# Rocket-Control3.net
KiCad netlist of a schematic drawn in EAGLE
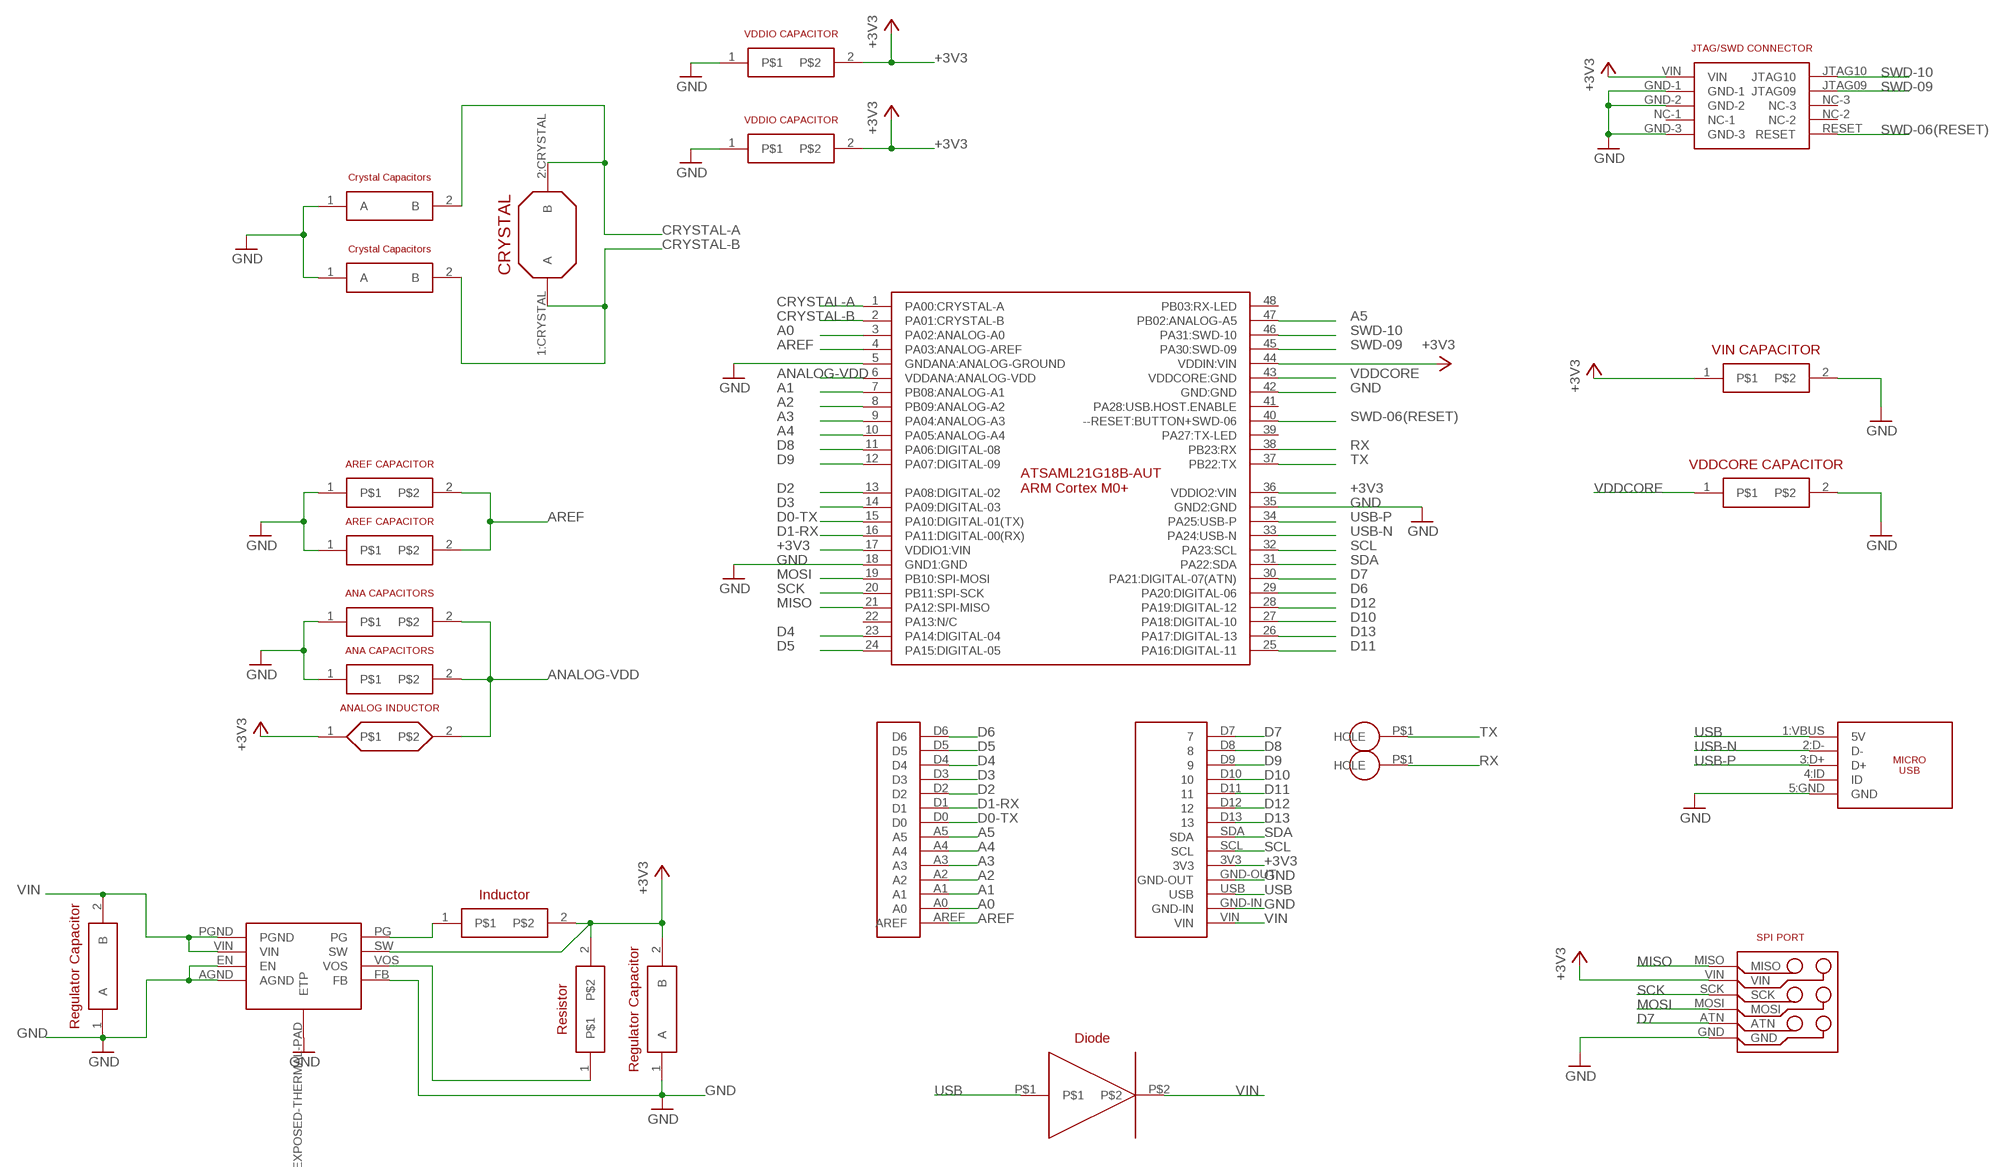
[diagram p0: schematic, sheet 1]

(export (version "E")
  (design (tool "Eeschema 10.0.6"))
  (components
    (comp (ref "U$1")
      (value "ATSAML21G18B-AUT")
      (footprint "eagle-import:TQFP48")
      (libsource (lib "eagle-import") (part "ATSAML21G18B-AUT"))
    )
    (comp (ref "U$2")
      (value "CRYSTAL-CAPACITORS")
      (footprint "eagle-import:C0603")
      (libsource (lib "eagle-import") (part "CRYSTAL-CAPACITORS"))
    )
    (comp (ref "U$3")
      (value "CRYSTAL-CAPACITORS")
      (footprint "eagle-import:C0603")
      (libsource (lib "eagle-import") (part "CRYSTAL-CAPACITORS"))
    )
    (comp (ref "U$4")
      (value "CRYSTAL")
      (footprint "eagle-import:4-SOJ_CRYSTAL")
      (libsource (lib "eagle-import") (part "CRYSTAL"))
    )
    (comp (ref "U$5")
      (value "REGULATOR")
      (footprint "eagle-import:8-WFDFN-EXPOSED-PAD")
      (libsource (lib "eagle-import") (part "REGULATOR"))
    )
    (comp (ref "U$6")
      (value "AREF-CAPACITORS")
      (footprint "eagle-import:C0603")
      (libsource (lib "eagle-import") (part "AREF-CAPACITORS"))
    )
    (comp (ref "U$7")
      (value "AREF-CAPACITORS")
      (footprint "eagle-import:C0603")
      (libsource (lib "eagle-import") (part "AREF-CAPACITORS"))
    )
    (comp (ref "U$8")
      (value "ANALOG-CAPACITORS")
      (footprint "eagle-import:C0603")
      (libsource (lib "eagle-import") (part "ANALOG-CAPACITORS"))
    )
    (comp (ref "U$9")
      (value "ANALOG-CAPACITORS")
      (footprint "eagle-import:C0603")
      (libsource (lib "eagle-import") (part "ANALOG-CAPACITORS"))
    )
    (comp (ref "U$10")
      (value "ANALOG-INDUCTOR")
      (footprint "eagle-import:C0603")
      (libsource (lib "eagle-import") (part "ANALOG-INDUCTOR"))
    )
    (comp (ref "U$11")
      (value "REGULATOR-CAPACITORS")
      (footprint "eagle-import:C0603")
      (libsource (lib "eagle-import") (part "REGULATOR-CAPACITORS"))
    )
    (comp (ref "U$12")
      (value "REGULATOR-CAPACITORS")
      (footprint "eagle-import:C0603")
      (libsource (lib "eagle-import") (part "REGULATOR-CAPACITORS"))
    )
    (comp (ref "U$13")
      (value "REGULATOR-INDUCTOR")
      (footprint "eagle-import:C0603")
      (libsource (lib "eagle-import") (part "REGULATOR-INDUCTOR"))
    )
    (comp (ref "U$14")
      (value "REGULATOR-RESISTOR")
      (footprint "eagle-import:C0603")
      (libsource (lib "eagle-import") (part "REGULATOR-RESISTOR"))
    )
    (comp (ref "U$15")
      (value "REGULATION-DIODE")
      (footprint "eagle-import:SOD-882")
      (libsource (lib "eagle-import") (part "REGULATION-DIODE"))
    )
    (comp (ref "U$16")
      (value "HEADER-HOLE")
      (footprint "eagle-import:HEADER-HOLE")
      (libsource (lib "eagle-import") (part "HEADER-HOLE"))
    )
    (comp (ref "U$17")
      (value "HEADER-HOLE")
      (footprint "eagle-import:HEADER-HOLE")
      (libsource (lib "eagle-import") (part "HEADER-HOLE"))
    )
    (comp (ref "U$21")
      (value "HEADER-SIDE-A")
      (footprint "eagle-import:HEADER-SIDE-A")
      (libsource (lib "eagle-import") (part "HEADER-SIDE-A"))
    )
    (comp (ref "U$22")
      (value "HEADER-SIDE-B")
      (footprint "eagle-import:HEADER-SIDE-B")
      (libsource (lib "eagle-import") (part "HEADER-SIDE-B"))
    )
    (comp (ref "U$26")
      (value "VDDIO-CAPACITOR")
      (footprint "eagle-import:C0402")
      (libsource (lib "eagle-import") (part "VDDIO-CAPACITOR"))
    )
    (comp (ref "U$35")
      (value "VDDIO-CAPACITOR")
      (footprint "eagle-import:C0402")
      (libsource (lib "eagle-import") (part "VDDIO-CAPACITOR"))
    )
    (comp (ref "U$38")
      (value "10118194-0001LF:MICRO-USB")
      (footprint "eagle-import:10118194-0001LF_MICRO-USB-B")
      (libsource (lib "eagle-import") (part "10118194-0001LF{colon}MICRO-USB"))
    )
    (comp (ref "U$41")
      (value "SPI-PORT")
      (footprint "eagle-import:SPI-PORT")
      (libsource (lib "eagle-import") (part "SPI-PORT"))
    )
    (comp (ref "U$56")
      (value "VDDCORE-CAPACITOR")
      (footprint "eagle-import:C0603")
      (libsource (lib "eagle-import") (part "VDDCORE-CAPACITOR"))
    )
    (comp (ref "U$57")
      (value "VIN-CAPACITOR")
      (footprint "eagle-import:C0603")
      (libsource (lib "eagle-import") (part "VIN-CAPACITOR"))
    )
    (comp (ref "U$61")
      (value "JTAG-MINI")
      (footprint "eagle-import:JTAG-MINI")
      (libsource (lib "eagle-import") (part "JTAG-MINI"))
    )
  )
  (nets
    (net (code "1") (name "+3V3") (class "Default")
      (node (ref "U$1") (pin "17") (pinfunction "VDDIO1:VIN_17") (pintype "bidirectional"))
      (node (ref "U$1") (pin "36") (pinfunction "VDDIO2:VIN_36") (pintype "bidirectional"))
      (node (ref "U$1") (pin "44") (pinfunction "VDDIN:VIN_44") (pintype "bidirectional"))
      (node (ref "U$10") (pin "1") (pinfunction "P$1_1") (pintype "bidirectional"))
      (node (ref "U$12") (pin "2") (pinfunction "B_2") (pintype "bidirectional"))
      (node (ref "U$13") (pin "2") (pinfunction "P$2_2") (pintype "bidirectional"))
      (node (ref "U$14") (pin "2") (pinfunction "P$2_2") (pintype "bidirectional"))
      (node (ref "U$22") (pin "3V3") (pinfunction "3V3_3V3") (pintype "bidirectional"))
      (node (ref "U$26") (pin "2") (pinfunction "P$2_2") (pintype "bidirectional"))
      (node (ref "U$35") (pin "2") (pinfunction "P$2_2") (pintype "bidirectional"))
      (node (ref "U$41") (pin "VIN") (pinfunction "VIN_VIN") (pintype "bidirectional"))
      (node (ref "U$5") (pin "SW") (pinfunction "SW_SW") (pintype "bidirectional"))
      (node (ref "U$57") (pin "1") (pinfunction "P$1_1") (pintype "bidirectional"))
      (node (ref "U$61") (pin "VIN") (pinfunction "VIN_VIN") (pintype "bidirectional"))
    )
    (net (code "2") (name "/A0") (class "Default")
      (node (ref "U$1") (pin "3") (pinfunction "PA02:ANALOG-A0_3") (pintype "bidirectional"))
      (node (ref "U$21") (pin "A0") (pinfunction "A0_A0") (pintype "bidirectional"))
    )
    (net (code "3") (name "/A1") (class "Default")
      (node (ref "U$1") (pin "7") (pinfunction "PB08:ANALOG-A1_7") (pintype "bidirectional"))
      (node (ref "U$21") (pin "A1") (pinfunction "A1_A1") (pintype "bidirectional"))
    )
    (net (code "4") (name "/A2") (class "Default")
      (node (ref "U$1") (pin "8") (pinfunction "PB09:ANALOG-A2_8") (pintype "bidirectional"))
      (node (ref "U$21") (pin "A2") (pinfunction "A2_A2") (pintype "bidirectional"))
    )
    (net (code "5") (name "/A3") (class "Default")
      (node (ref "U$1") (pin "9") (pinfunction "PA04:ANALOG-A3_9") (pintype "bidirectional"))
      (node (ref "U$21") (pin "A3") (pinfunction "A3_A3") (pintype "bidirectional"))
    )
    (net (code "6") (name "/A4") (class "Default")
      (node (ref "U$1") (pin "10") (pinfunction "PA05:ANALOG-A4_10") (pintype "bidirectional"))
      (node (ref "U$21") (pin "A4") (pinfunction "A4_A4") (pintype "bidirectional"))
    )
    (net (code "7") (name "/A5") (class "Default")
      (node (ref "U$1") (pin "47") (pinfunction "PB02:ANALOG-A5_47") (pintype "bidirectional"))
      (node (ref "U$21") (pin "A5") (pinfunction "A5_A5") (pintype "bidirectional"))
    )
    (net (code "8") (name "/ANALOG-VDD") (class "Default")
      (node (ref "U$1") (pin "6") (pinfunction "VDDANA:ANALOG-VDD_6") (pintype "bidirectional"))
      (node (ref "U$10") (pin "2") (pinfunction "P$2_2") (pintype "bidirectional"))
      (node (ref "U$8") (pin "2") (pinfunction "P$2_2") (pintype "bidirectional"))
      (node (ref "U$9") (pin "2") (pinfunction "P$2_2") (pintype "bidirectional"))
    )
    (net (code "9") (name "/AREF") (class "Default")
      (node (ref "U$1") (pin "4") (pinfunction "PA03:ANALOG-AREF_4") (pintype "bidirectional"))
      (node (ref "U$21") (pin "AREF") (pinfunction "AREF_AREF") (pintype "bidirectional"))
      (node (ref "U$6") (pin "2") (pinfunction "P$2_2") (pintype "bidirectional"))
      (node (ref "U$7") (pin "2") (pinfunction "P$2_2") (pintype "bidirectional"))
    )
    (net (code "10") (name "/CRYSTAL-A") (class "Default")
      (node (ref "U$1") (pin "1") (pinfunction "PA00:CRYSTAL-A_1") (pintype "bidirectional"))
      (node (ref "U$2") (pin "2") (pinfunction "B_2") (pintype "bidirectional"))
      (node (ref "U$4") (pin "2:CRYSTAL") (pinfunction "B_2:CRYSTAL") (pintype "bidirectional"))
    )
    (net (code "11") (name "/CRYSTAL-B") (class "Default")
      (node (ref "U$1") (pin "2") (pinfunction "PA01:CRYSTAL-B_2") (pintype "bidirectional"))
      (node (ref "U$3") (pin "2") (pinfunction "B_2") (pintype "bidirectional"))
      (node (ref "U$4") (pin "1:CRYSTAL") (pinfunction "A_1:CRYSTAL") (pintype "bidirectional"))
    )
    (net (code "12") (name "/D0-TX") (class "Default")
      (node (ref "U$1") (pin "15") (pinfunction "PA10:DIGITAL-01(TX)_15") (pintype "bidirectional"))
      (node (ref "U$21") (pin "D0") (pinfunction "D0_D0") (pintype "bidirectional"))
    )
    (net (code "13") (name "/D1-RX") (class "Default")
      (node (ref "U$1") (pin "16") (pinfunction "PA11:DIGITAL-00(RX)_16") (pintype "bidirectional"))
      (node (ref "U$21") (pin "D1") (pinfunction "D1_D1") (pintype "bidirectional"))
    )
    (net (code "14") (name "/D2") (class "Default")
      (node (ref "U$1") (pin "13") (pinfunction "PA08:DIGITAL-02_13") (pintype "bidirectional"))
      (node (ref "U$21") (pin "D2") (pinfunction "D2_D2") (pintype "bidirectional"))
    )
    (net (code "15") (name "/D3") (class "Default")
      (node (ref "U$1") (pin "14") (pinfunction "PA09:DIGITAL-03_14") (pintype "bidirectional"))
      (node (ref "U$21") (pin "D3") (pinfunction "D3_D3") (pintype "bidirectional"))
    )
    (net (code "16") (name "/D4") (class "Default")
      (node (ref "U$1") (pin "23") (pinfunction "PA14:DIGITAL-04_23") (pintype "bidirectional"))
      (node (ref "U$21") (pin "D4") (pinfunction "D4_D4") (pintype "bidirectional"))
    )
    (net (code "17") (name "/D5") (class "Default")
      (node (ref "U$1") (pin "24") (pinfunction "PA15:DIGITAL-05_24") (pintype "bidirectional"))
      (node (ref "U$21") (pin "D5") (pinfunction "D5_D5") (pintype "bidirectional"))
    )
    (net (code "18") (name "/D6") (class "Default")
      (node (ref "U$1") (pin "29") (pinfunction "PA20:DIGITAL-06_29") (pintype "bidirectional"))
      (node (ref "U$21") (pin "D6") (pinfunction "D6_D6") (pintype "bidirectional"))
    )
    (net (code "19") (name "/D7") (class "Default")
      (node (ref "U$1") (pin "30") (pinfunction "PA21:DIGITAL-07(ATN)_30") (pintype "bidirectional"))
      (node (ref "U$22") (pin "D7") (pinfunction "7_D7") (pintype "bidirectional"))
      (node (ref "U$41") (pin "ATN") (pinfunction "ATN_ATN") (pintype "bidirectional"))
    )
    (net (code "20") (name "/D8") (class "Default")
      (node (ref "U$1") (pin "11") (pinfunction "PA06:DIGITAL-08_11") (pintype "bidirectional"))
      (node (ref "U$22") (pin "D8") (pinfunction "8_D8") (pintype "bidirectional"))
    )
    (net (code "21") (name "/D9") (class "Default")
      (node (ref "U$1") (pin "12") (pinfunction "PA07:DIGITAL-09_12") (pintype "bidirectional"))
      (node (ref "U$22") (pin "D9") (pinfunction "9_D9") (pintype "bidirectional"))
    )
    (net (code "22") (name "/D10") (class "Default")
      (node (ref "U$1") (pin "27") (pinfunction "PA18:DIGITAL-10_27") (pintype "bidirectional"))
      (node (ref "U$22") (pin "D10") (pinfunction "10_D10") (pintype "bidirectional"))
    )
    (net (code "23") (name "/D11") (class "Default")
      (node (ref "U$1") (pin "25") (pinfunction "PA16:DIGITAL-11_25") (pintype "bidirectional"))
      (node (ref "U$22") (pin "D11") (pinfunction "11_D11") (pintype "bidirectional"))
    )
    (net (code "24") (name "/D12") (class "Default")
      (node (ref "U$1") (pin "28") (pinfunction "PA19:DIGITAL-12_28") (pintype "bidirectional"))
      (node (ref "U$22") (pin "D12") (pinfunction "12_D12") (pintype "bidirectional"))
    )
    (net (code "25") (name "/D13") (class "Default")
      (node (ref "U$1") (pin "26") (pinfunction "PA17:DIGITAL-13_26") (pintype "bidirectional"))
      (node (ref "U$22") (pin "D13") (pinfunction "13_D13") (pintype "bidirectional"))
    )
    (net (code "26") (name "/MISO") (class "Default")
      (node (ref "U$1") (pin "21") (pinfunction "PA12:SPI-MISO_21") (pintype "bidirectional"))
      (node (ref "U$41") (pin "MISO") (pinfunction "MISO_MISO") (pintype "bidirectional"))
    )
    (net (code "27") (name "/MOSI") (class "Default")
      (node (ref "U$1") (pin "19") (pinfunction "PB10:SPI-MOSI_19") (pintype "bidirectional"))
      (node (ref "U$41") (pin "MOSI") (pinfunction "MOSI_MOSI") (pintype "bidirectional"))
    )
    (net (code "28") (name "/RX") (class "Default")
      (node (ref "U$1") (pin "38") (pinfunction "PB23:RX_38") (pintype "bidirectional"))
      (node (ref "U$17") (pin "P$1") (pinfunction "HOLE_P$1") (pintype "bidirectional"))
    )
    (net (code "29") (name "/SCK") (class "Default")
      (node (ref "U$1") (pin "20") (pinfunction "PB11:SPI-SCK_20") (pintype "bidirectional"))
      (node (ref "U$41") (pin "SCK") (pinfunction "SCK_SCK") (pintype "bidirectional"))
    )
    (net (code "30") (name "/SCL") (class "Default")
      (node (ref "U$1") (pin "32") (pinfunction "PA23:SCL_32") (pintype "bidirectional"))
      (node (ref "U$22") (pin "SCL") (pinfunction "SCL_SCL") (pintype "bidirectional"))
    )
    (net (code "31") (name "/SDA") (class "Default")
      (node (ref "U$1") (pin "31") (pinfunction "PA22:SDA_31") (pintype "bidirectional"))
      (node (ref "U$22") (pin "SDA") (pinfunction "SDA_SDA") (pintype "bidirectional"))
    )
    (net (code "32") (name "/SWD-06(RESET)") (class "Default")
      (node (ref "U$1") (pin "40") (pinfunction "--RESET:BUTTON+SWD-06_40") (pintype "bidirectional"))
      (node (ref "U$61") (pin "RESET") (pinfunction "RESET_RESET") (pintype "bidirectional"))
    )
    (net (code "33") (name "/SWD-09") (class "Default")
      (node (ref "U$1") (pin "45") (pinfunction "PA30:SWD-09_45") (pintype "bidirectional"))
      (node (ref "U$61") (pin "JTAG09") (pinfunction "JTAG09_JTAG09") (pintype "bidirectional"))
    )
    (net (code "34") (name "/SWD-10") (class "Default")
      (node (ref "U$1") (pin "46") (pinfunction "PA31:SWD-10_46") (pintype "bidirectional"))
      (node (ref "U$61") (pin "JTAG10") (pinfunction "JTAG10_JTAG10") (pintype "bidirectional"))
    )
    (net (code "35") (name "/TX") (class "Default")
      (node (ref "U$1") (pin "37") (pinfunction "PB22:TX_37") (pintype "bidirectional"))
      (node (ref "U$16") (pin "P$1") (pinfunction "HOLE_P$1") (pintype "bidirectional"))
    )
    (net (code "36") (name "/USB") (class "Default")
      (node (ref "U$15") (pin "P$1") (pinfunction "P$1_P$1") (pintype "bidirectional"))
      (node (ref "U$22") (pin "USB") (pinfunction "USB_USB") (pintype "bidirectional"))
      (node (ref "U$38") (pin "1:VBUS") (pinfunction "5V_1:VBUS") (pintype "bidirectional"))
    )
    (net (code "37") (name "/USB-N") (class "Default")
      (node (ref "U$1") (pin "33") (pinfunction "PA24:USB-N_33") (pintype "bidirectional"))
      (node (ref "U$38") (pin "2:D-") (pinfunction "D-_2:D-") (pintype "bidirectional"))
    )
    (net (code "38") (name "/USB-P") (class "Default")
      (node (ref "U$1") (pin "34") (pinfunction "PA25:USB-P_34") (pintype "bidirectional"))
      (node (ref "U$38") (pin "3:D+") (pinfunction "D+_3:D+") (pintype "bidirectional"))
    )
    (net (code "39") (name "/VDDCORE") (class "Default")
      (node (ref "U$1") (pin "43") (pinfunction "VDDCORE:GND_43") (pintype "bidirectional"))
      (node (ref "U$56") (pin "1") (pinfunction "P$1_1") (pintype "bidirectional"))
    )
    (net (code "40") (name "/VIN") (class "Default")
      (node (ref "U$11") (pin "2") (pinfunction "B_2") (pintype "bidirectional"))
      (node (ref "U$15") (pin "P$2") (pinfunction "P$2_P$2") (pintype "bidirectional"))
      (node (ref "U$22") (pin "VIN") (pinfunction "VIN_VIN") (pintype "bidirectional"))
      (node (ref "U$5") (pin "PGND") (pinfunction "PGND_PGND") (pintype "bidirectional"))
      (node (ref "U$5") (pin "VIN") (pinfunction "VIN_VIN") (pintype "bidirectional"))
    )
    (net (code "41") (name "GND") (class "Default")
      (node (ref "U$1") (pin "18") (pinfunction "GND1:GND_18") (pintype "bidirectional"))
      (node (ref "U$1") (pin "35") (pinfunction "GND2:GND_35") (pintype "bidirectional"))
      (node (ref "U$1") (pin "42") (pinfunction "GND:GND_42") (pintype "bidirectional"))
      (node (ref "U$1") (pin "5") (pinfunction "GNDANA:ANALOG-GROUND_5") (pintype "bidirectional"))
      (node (ref "U$11") (pin "1") (pinfunction "A_1") (pintype "bidirectional"))
      (node (ref "U$12") (pin "1") (pinfunction "A_1") (pintype "bidirectional"))
      (node (ref "U$2") (pin "1") (pinfunction "A_1") (pintype "bidirectional"))
      (node (ref "U$22") (pin "GND-IN") (pinfunction "GND-IN_GND-IN") (pintype "bidirectional"))
      (node (ref "U$22") (pin "GND-OUT") (pinfunction "GND-OUT_GND-OUT") (pintype "bidirectional"))
      (node (ref "U$26") (pin "1") (pinfunction "P$1_1") (pintype "bidirectional"))
      (node (ref "U$3") (pin "1") (pinfunction "A_1") (pintype "bidirectional"))
      (node (ref "U$35") (pin "1") (pinfunction "P$1_1") (pintype "bidirectional"))
      (node (ref "U$38") (pin "5:GND") (pinfunction "GND_5:GND") (pintype "bidirectional"))
      (node (ref "U$41") (pin "GND") (pinfunction "GND_GND") (pintype "bidirectional"))
      (node (ref "U$5") (pin "AGND") (pinfunction "AGND_AGND") (pintype "bidirectional"))
      (node (ref "U$5") (pin "EN") (pinfunction "EN_EN") (pintype "bidirectional"))
      (node (ref "U$5") (pin "EXPOSED-THERMAL-PAD") (pinfunction "ETP_EXPOSED-THERMAL-PAD") (pintype "bidirectional"))
      (node (ref "U$5") (pin "FB") (pinfunction "FB_FB") (pintype "bidirectional"))
      (node (ref "U$56") (pin "2") (pinfunction "P$2_2") (pintype "bidirectional"))
      (node (ref "U$57") (pin "2") (pinfunction "P$2_2") (pintype "bidirectional"))
      (node (ref "U$6") (pin "1") (pinfunction "P$1_1") (pintype "bidirectional"))
      (node (ref "U$61") (pin "GND-1") (pinfunction "GND-1_GND-1") (pintype "bidirectional"))
      (node (ref "U$61") (pin "GND-2") (pinfunction "GND-2_GND-2") (pintype "bidirectional"))
      (node (ref "U$61") (pin "GND-3") (pinfunction "GND-3_GND-3") (pintype "bidirectional"))
      (node (ref "U$7") (pin "1") (pinfunction "P$1_1") (pintype "bidirectional"))
      (node (ref "U$8") (pin "1") (pinfunction "P$1_1") (pintype "bidirectional"))
      (node (ref "U$9") (pin "1") (pinfunction "P$1_1") (pintype "bidirectional"))
    )
    (net (code "42") (name "Net-(U$13-P$1)") (class "Default")
      (node (ref "U$13") (pin "1") (pinfunction "P$1_1") (pintype "bidirectional"))
      (node (ref "U$5") (pin "PG") (pinfunction "PG_PG") (pintype "bidirectional"))
    )
    (net (code "43") (name "Net-(U$14-P$1)") (class "Default")
      (node (ref "U$14") (pin "1") (pinfunction "P$1_1") (pintype "bidirectional"))
      (node (ref "U$5") (pin "VOS") (pinfunction "VOS_VOS") (pintype "bidirectional"))
    )
    (net (code "44") (name "unconnected-(U$1-PA13:N{slash}C-Pad22)") (class "Default")
      (node (ref "U$1") (pin "22") (pinfunction "PA13:N/C_22") (pintype "bidirectional"))
    )
    (net (code "45") (name "unconnected-(U$1-PA27:TX-LED-Pad39)") (class "Default")
      (node (ref "U$1") (pin "39") (pinfunction "PA27:TX-LED_39") (pintype "bidirectional"))
    )
    (net (code "46") (name "unconnected-(U$1-PA28:USB.HOST.ENABLE-Pad41)") (class "Default")
      (node (ref "U$1") (pin "41") (pinfunction "PA28:USB.HOST.ENABLE_41") (pintype "bidirectional"))
    )
    (net (code "47") (name "unconnected-(U$1-PB03:RX-LED-Pad48)") (class "Default")
      (node (ref "U$1") (pin "48") (pinfunction "PB03:RX-LED_48") (pintype "bidirectional"))
    )
    (net (code "48") (name "unconnected-(U$38-ID-Pad4:ID)") (class "Default")
      (node (ref "U$38") (pin "4:ID") (pinfunction "ID_4:ID") (pintype "bidirectional"))
    )
    (net (code "49") (name "unconnected-(U$61-PadNC-1)") (class "Default")
      (node (ref "U$61") (pin "NC-1") (pinfunction "NC-1_NC-1") (pintype "bidirectional"))
    )
    (net (code "50") (name "unconnected-(U$61-PadNC-2)") (class "Default")
      (node (ref "U$61") (pin "NC-2") (pinfunction "NC-2_NC-2") (pintype "bidirectional"))
    )
    (net (code "51") (name "unconnected-(U$61-PadNC-3)") (class "Default")
      (node (ref "U$61") (pin "NC-3") (pinfunction "NC-3_NC-3") (pintype "bidirectional"))
    )
  )
)
